# SCH_CLController.net
KiCad netlist of a schematic drawn in EasyEDA
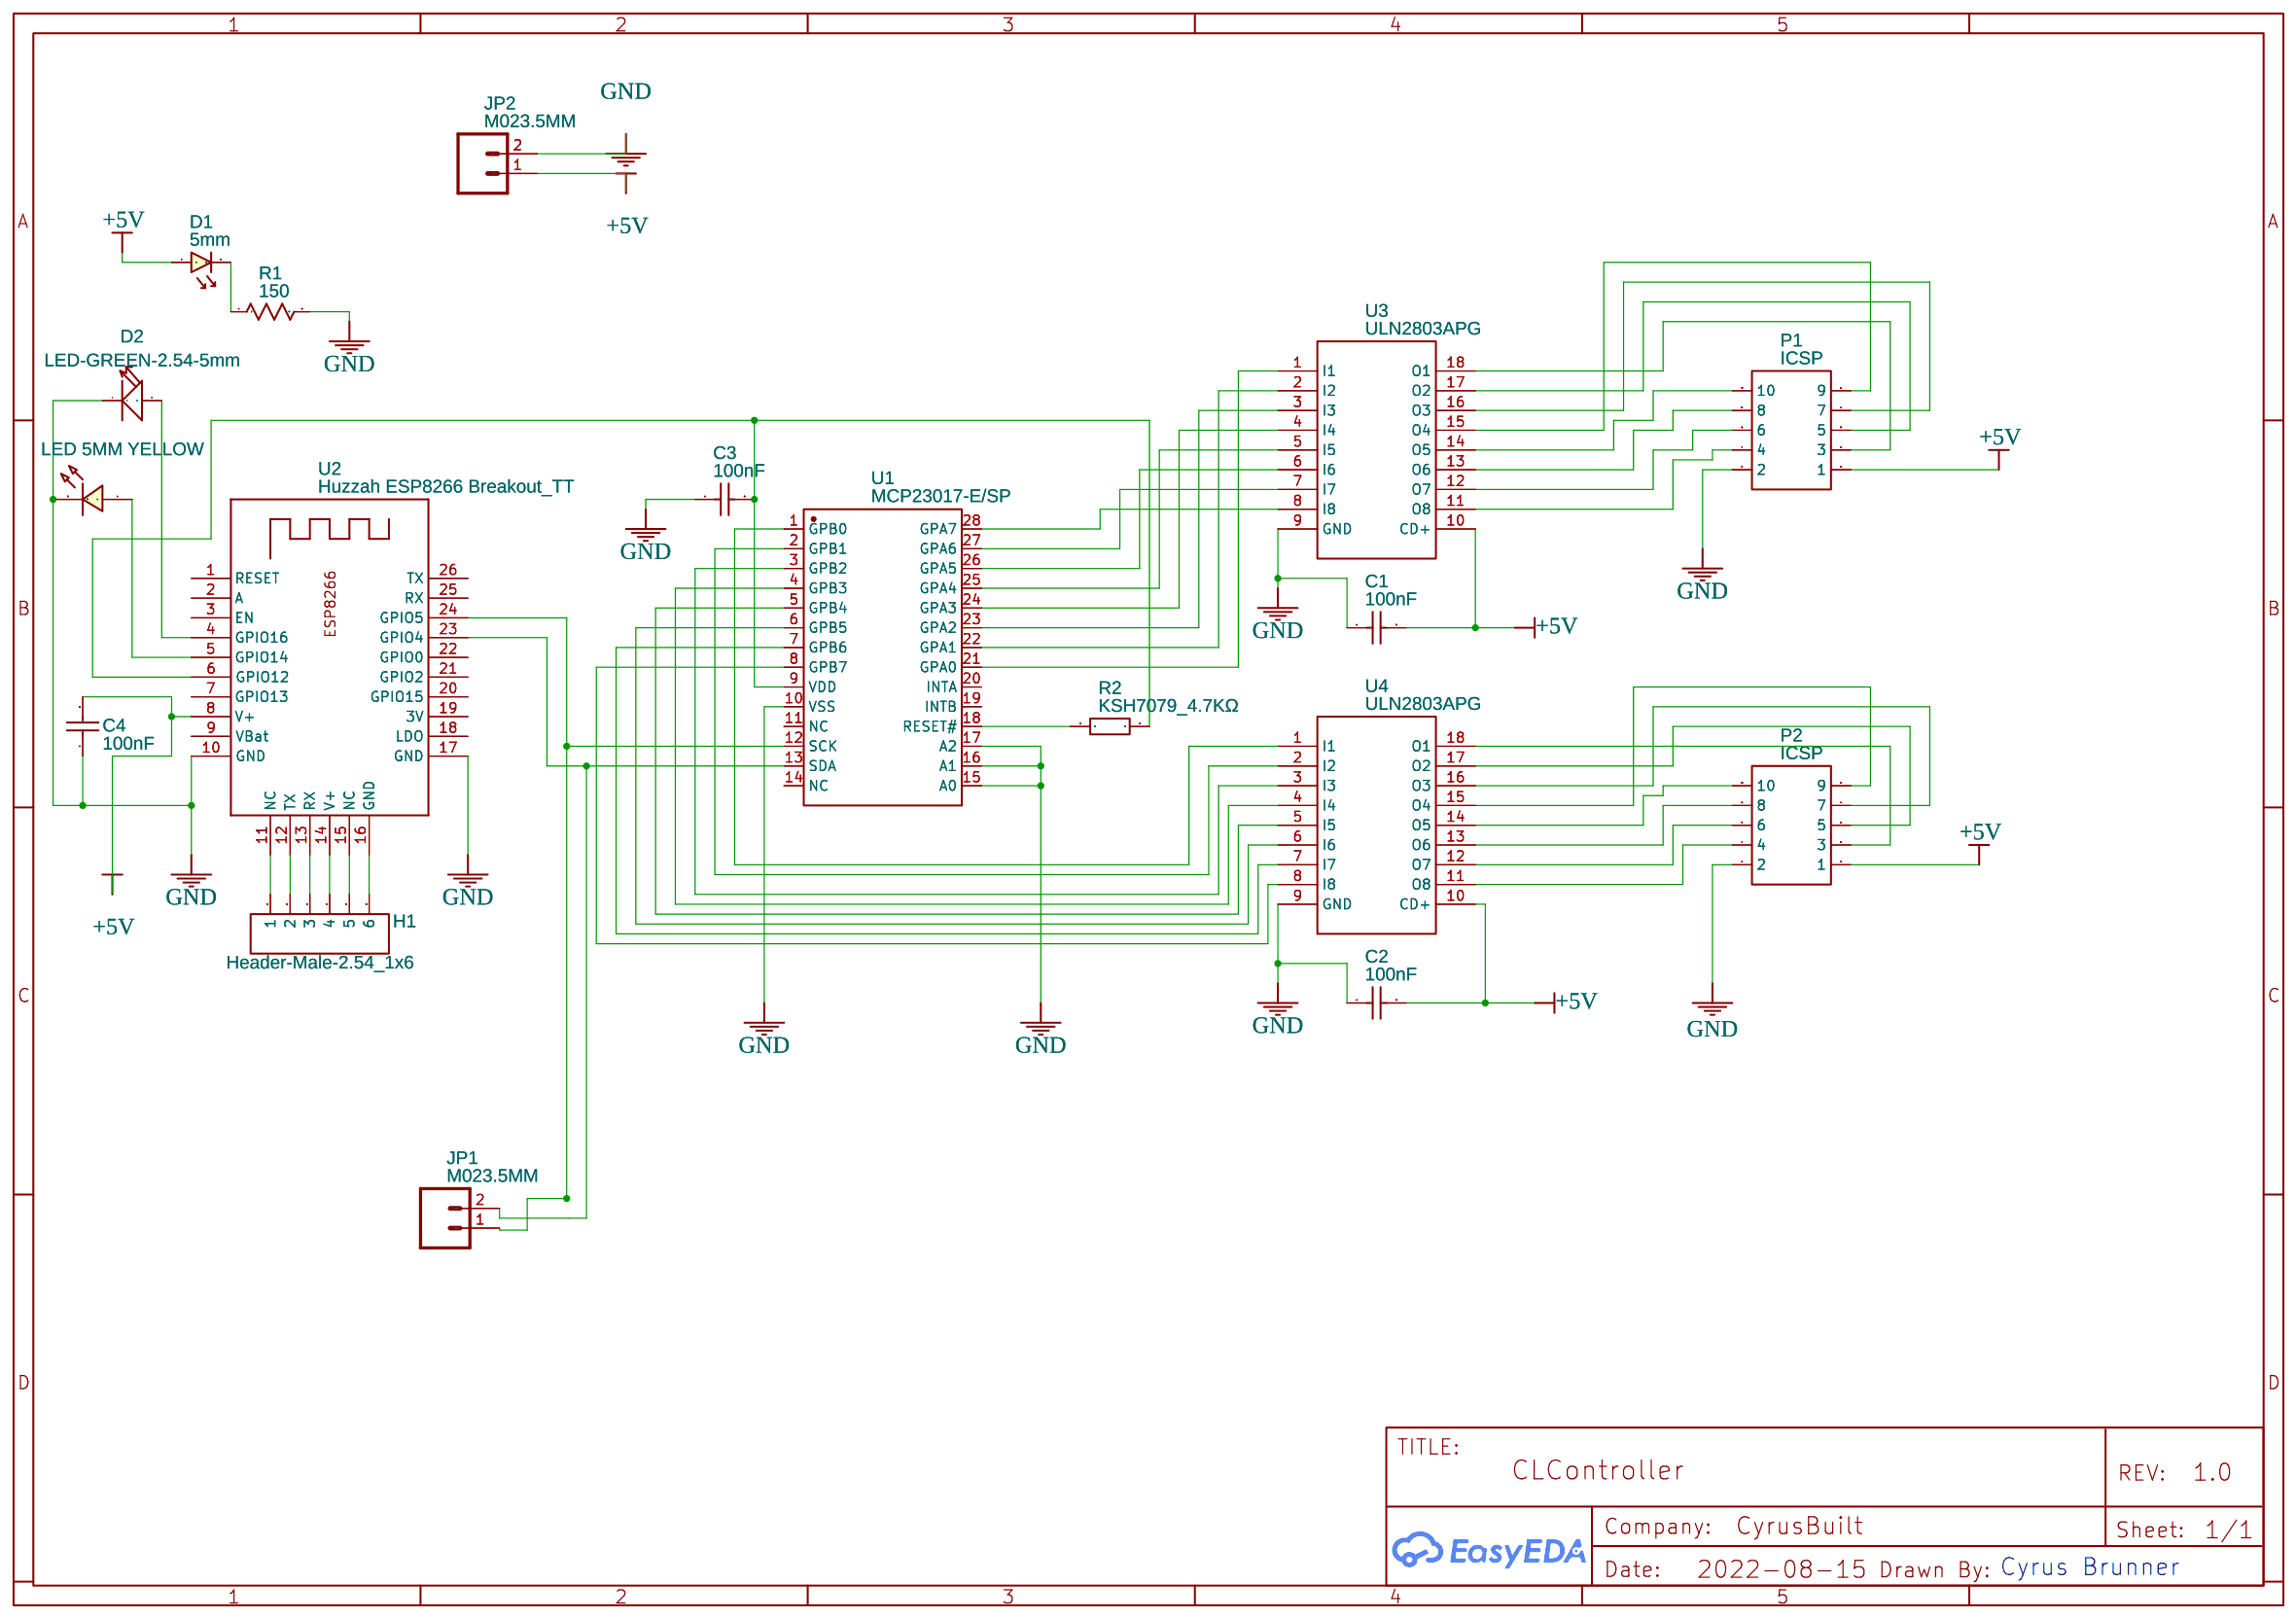
[diagram p0: schematic sheet]

(export (version "E")
  (design (tool "Eeschema 10.0.6"))
  (components
    (comp (ref "1") (value "LED 5MM YELLOW") (libsource (lib "") (part "LED 5MM YELLOW")))
    (comp (ref "C1")
      (value "100nF")
      (fields
        (field (name "BOM_Manufacturer Part") "CT4-0805Y104M500")
        (field (name "BOM_Supplier Part") "C46756")
      )
      (libsource (lib "") (part "100nF"))
    )
    (comp (ref "C2")
      (value "100nF")
      (fields
        (field (name "BOM_Manufacturer Part") "CT4-0805Y104M500")
        (field (name "BOM_Supplier Part") "C46756")
      )
      (libsource (lib "") (part "100nF"))
    )
    (comp (ref "C3")
      (value "100nF")
      (fields
        (field (name "BOM_Manufacturer Part") "CT4-0805Y104M500")
        (field (name "BOM_Supplier Part") "C46756")
      )
      (libsource (lib "") (part "100nF"))
    )
    (comp (ref "C4")
      (value "100nF")
      (fields
        (field (name "BOM_Manufacturer Part") "CT4-0805Y104M500")
        (field (name "BOM_Supplier Part") "C46756")
      )
      (libsource (lib "") (part "100nF_1"))
    )
    (comp (ref "D1")
      (value "5mm")
      (fields (field (name "BOM_Manufacturer Part") "L-1503EC") (field (name "BOM_Supplier Part") "1003201"))
      (libsource (lib "") (part "L-1503EC"))
    )
    (comp (ref "D2")
      (value "LED-GREEN-2.54-5mm")
      (fields (field (name "BOM_Manufacturer Part") "503UOC"))
      (libsource (lib "") (part "LED-GREEN-2.54-5mm"))
    )
    (comp (ref "H1")
      (value "Header-Male-2.54_1x6")
      (fields (field (name "BOM_Supplier Part") "C37208"))
      (libsource (lib "") (part "Header-Male-2.54_1x6"))
    )
    (comp (ref "JP1") (value "M023.5MM") (libsource (lib "") (part "M023.5MM")))
    (comp (ref "JP2") (value "M023.5MM") (libsource (lib "") (part "M023.5MM")))
    (comp (ref "P1")
      (value "ICSP")
      (fields
        (field (name "BOM_Manufacturer Part") "IDC Box 2.54mm 2X5P")
        (field (name "BOM_Supplier Part") "C5665")
      )
      (libsource (lib "") (part "ICSP"))
    )
    (comp (ref "P2")
      (value "ICSP")
      (fields
        (field (name "BOM_Manufacturer Part") "IDC Box 2.54mm 2X5P")
        (field (name "BOM_Supplier Part") "C5665")
      )
      (libsource (lib "") (part "ICSP"))
    )
    (comp (ref "R1")
      (value "150")
      (fields
        (field (name "BOM_Manufacturer Part") "MCF 0.25W 150R")
        (field (name "BOM_Supplier Part") "9339175")
      )
      (libsource (lib "") (part "MCF 0.25W 150R"))
    )
    (comp (ref "R2")
      (value "KSH7079_4.7KΩ")
      (fields
        (field (name "BOM_Manufacturer Part") "MFR0W4F2200A50")
        (field (name "BOM_Supplier Part") "E57439")
      )
      (libsource (lib "") (part "KSH7079_4.7KΩ"))
    )
    (comp (ref "U1")
      (value "MCP23017-E/SP")
      (fields (field (name "BOM_Supplier Part") "C647352"))
      (libsource (lib "") (part "MCP23017-E/SP"))
    )
    (comp (ref "U2")
      (value "Huzzah ESP8266 Breakout_TT")
      (libsource (lib "") (part "Huzzah ESP8266 Breakout_TT"))
    )
    (comp (ref "U3")
      (value "ULN2803APG")
      (fields (field (name "BOM_Supplier Part") "C5252"))
      (libsource (lib "") (part "ULN2803APG"))
    )
    (comp (ref "U4")
      (value "ULN2803APG")
      (fields (field (name "BOM_Supplier Part") "C5252"))
      (libsource (lib "") (part "ULN2803APG"))
    )
  )
  (nets
    (net (code "1") (name "+5V") (class "Default")
      (node (ref "C1") (pin "2") (pinfunction "2_2") (pintype "input"))
      (node (ref "C2") (pin "2") (pinfunction "2_2") (pintype "input"))
      (node (ref "C4") (pin "2") (pinfunction "2_2") (pintype "input"))
      (node (ref "D1") (pin "1") (pinfunction "1_1") (pintype "unspecified"))
      (node (ref "JP2") (pin "1") (pinfunction "1_1") (pintype "bidirectional"))
      (node (ref "P1") (pin "1") (pinfunction "1_1") (pintype "unspecified"))
      (node (ref "P2") (pin "1") (pinfunction "1_1") (pintype "unspecified"))
      (node (ref "U2") (pin "8") (pinfunction "V+_8") (pintype "bidirectional"))
      (node (ref "U3") (pin "10") (pinfunction "CD+_10") (pintype "unspecified"))
      (node (ref "U4") (pin "10") (pinfunction "CD+_10") (pintype "unspecified"))
    )
    (net (code "2") (name "GND") (class "Default")
      (node (ref "1") (pin "2") (pinfunction "2_2") (pintype "unspecified"))
      (node (ref "C1") (pin "1") (pinfunction "1_1") (pintype "input"))
      (node (ref "C2") (pin "1") (pinfunction "1_1") (pintype "input"))
      (node (ref "C3") (pin "1") (pinfunction "1_1") (pintype "input"))
      (node (ref "C4") (pin "1") (pinfunction "1_1") (pintype "input"))
      (node (ref "D2") (pin "-") (pinfunction "-_-") (pintype "unspecified"))
      (node (ref "JP2") (pin "2") (pinfunction "2_2") (pintype "bidirectional"))
      (node (ref "P1") (pin "2") (pinfunction "2_2") (pintype "unspecified"))
      (node (ref "P2") (pin "2") (pinfunction "2_2") (pintype "unspecified"))
      (node (ref "R1") (pin "2") (pinfunction "2_2") (pintype "unspecified"))
      (node (ref "U1") (pin "10") (pinfunction "VSS_10") (pintype "unspecified"))
      (node (ref "U1") (pin "15") (pinfunction "A0_15") (pintype "unspecified"))
      (node (ref "U1") (pin "16") (pinfunction "A1_16") (pintype "unspecified"))
      (node (ref "U1") (pin "17") (pinfunction "A2_17") (pintype "unspecified"))
      (node (ref "U2") (pin "10") (pinfunction "GND_10") (pintype "unspecified"))
      (node (ref "U2") (pin "17") (pinfunction "GND_17") (pintype "unspecified"))
      (node (ref "U3") (pin "9") (pinfunction "GND_9") (pintype "passive"))
      (node (ref "U4") (pin "9") (pinfunction "GND_9") (pintype "passive"))
    )
    (net (code "3") (name "Net-(D1-Pad2)") (class "Default")
      (node (ref "D1") (pin "2") (pinfunction "2_2") (pintype "unspecified"))
      (node (ref "R1") (pin "1") (pinfunction "1_1") (pintype "unspecified"))
    )
    (net (code "4") (name "Net-(H1-Pad1)") (class "Default")
      (node (ref "H1") (pin "1") (pinfunction "1_1") (pintype "input"))
      (node (ref "U2") (pin "11") (pinfunction "NC_11") (pintype "unspecified"))
    )
    (net (code "5") (name "Net-(H1-Pad2)") (class "Default")
      (node (ref "H1") (pin "2") (pinfunction "2_2") (pintype "input"))
      (node (ref "U2") (pin "12") (pinfunction "TX_12") (pintype "unspecified"))
    )
    (net (code "6") (name "Net-(H1-Pad3)") (class "Default")
      (node (ref "H1") (pin "3") (pinfunction "3_3") (pintype "input"))
      (node (ref "U2") (pin "13") (pinfunction "RX_13") (pintype "unspecified"))
    )
    (net (code "7") (name "Net-(H1-Pad4)") (class "Default")
      (node (ref "H1") (pin "4") (pinfunction "4_4") (pintype "input"))
      (node (ref "U2") (pin "14") (pinfunction "V+_14") (pintype "unspecified"))
    )
    (net (code "8") (name "Net-(H1-Pad5)") (class "Default")
      (node (ref "H1") (pin "5") (pinfunction "5_5") (pintype "input"))
      (node (ref "U2") (pin "15") (pinfunction "NC_15") (pintype "unspecified"))
    )
    (net (code "9") (name "Net-(H1-Pad6)") (class "Default")
      (node (ref "H1") (pin "6") (pinfunction "6_6") (pintype "input"))
      (node (ref "U2") (pin "16") (pinfunction "GND_16") (pintype "unspecified"))
    )
    (net (code "10") (name "Net-(U1-GPA0)") (class "Default")
      (node (ref "U1") (pin "21") (pinfunction "GPA0_21") (pintype "unspecified"))
      (node (ref "U3") (pin "1") (pinfunction "I1_1") (pintype "input"))
    )
    (net (code "11") (name "Net-(U1-GPA1)") (class "Default")
      (node (ref "U1") (pin "22") (pinfunction "GPA1_22") (pintype "unspecified"))
      (node (ref "U3") (pin "2") (pinfunction "I2_2") (pintype "input"))
    )
    (net (code "12") (name "Net-(U1-GPA2)") (class "Default")
      (node (ref "U1") (pin "23") (pinfunction "GPA2_23") (pintype "unspecified"))
      (node (ref "U3") (pin "3") (pinfunction "I3_3") (pintype "input"))
    )
    (net (code "13") (name "Net-(U1-GPA3)") (class "Default")
      (node (ref "U1") (pin "24") (pinfunction "GPA3_24") (pintype "unspecified"))
      (node (ref "U3") (pin "4") (pinfunction "I4_4") (pintype "input"))
    )
    (net (code "14") (name "Net-(U1-GPA4)") (class "Default")
      (node (ref "U1") (pin "25") (pinfunction "GPA4_25") (pintype "unspecified"))
      (node (ref "U3") (pin "5") (pinfunction "I5_5") (pintype "input"))
    )
    (net (code "15") (name "Net-(U1-GPA5)") (class "Default")
      (node (ref "U1") (pin "26") (pinfunction "GPA5_26") (pintype "unspecified"))
      (node (ref "U3") (pin "6") (pinfunction "I6_6") (pintype "input"))
    )
    (net (code "16") (name "Net-(U1-GPA6)") (class "Default")
      (node (ref "U1") (pin "27") (pinfunction "GPA6_27") (pintype "unspecified"))
      (node (ref "U3") (pin "7") (pinfunction "I7_7") (pintype "input"))
    )
    (net (code "17") (name "Net-(U1-GPA7)") (class "Default")
      (node (ref "U1") (pin "28") (pinfunction "GPA7_28") (pintype "unspecified"))
      (node (ref "U3") (pin "8") (pinfunction "I8_8") (pintype "input"))
    )
    (net (code "18") (name "Net-(U1-GPB0)") (class "Default")
      (node (ref "U1") (pin "1") (pinfunction "GPB0_1") (pintype "unspecified"))
      (node (ref "U4") (pin "1") (pinfunction "I1_1") (pintype "input"))
    )
    (net (code "19") (name "Net-(U1-GPB1)") (class "Default")
      (node (ref "U1") (pin "2") (pinfunction "GPB1_2") (pintype "unspecified"))
      (node (ref "U4") (pin "2") (pinfunction "I2_2") (pintype "input"))
    )
    (net (code "20") (name "Net-(U1-GPB2)") (class "Default")
      (node (ref "U1") (pin "3") (pinfunction "GPB2_3") (pintype "unspecified"))
      (node (ref "U4") (pin "3") (pinfunction "I3_3") (pintype "input"))
    )
    (net (code "21") (name "Net-(U1-GPB3)") (class "Default")
      (node (ref "U1") (pin "4") (pinfunction "GPB3_4") (pintype "unspecified"))
      (node (ref "U4") (pin "4") (pinfunction "I4_4") (pintype "input"))
    )
    (net (code "22") (name "Net-(U1-GPB4)") (class "Default")
      (node (ref "U1") (pin "5") (pinfunction "GPB4_5") (pintype "unspecified"))
      (node (ref "U4") (pin "5") (pinfunction "I5_5") (pintype "input"))
    )
    (net (code "23") (name "Net-(U1-GPB5)") (class "Default")
      (node (ref "U1") (pin "6") (pinfunction "GPB5_6") (pintype "unspecified"))
      (node (ref "U4") (pin "6") (pinfunction "I6_6") (pintype "input"))
    )
    (net (code "24") (name "Net-(U1-GPB6)") (class "Default")
      (node (ref "U1") (pin "7") (pinfunction "GPB6_7") (pintype "unspecified"))
      (node (ref "U4") (pin "7") (pinfunction "I7_7") (pintype "input"))
    )
    (net (code "25") (name "Net-(U1-GPB7)") (class "Default")
      (node (ref "U1") (pin "8") (pinfunction "GPB7_8") (pintype "unspecified"))
      (node (ref "U4") (pin "8") (pinfunction "I8_8") (pintype "input"))
    )
    (net (code "26") (name "Net-(U1-RESET#)") (class "Default")
      (node (ref "R2") (pin "1") (pinfunction "1_1") (pintype "input"))
      (node (ref "U1") (pin "18") (pinfunction "RESET#_18") (pintype "unspecified"))
    )
    (net (code "27") (name "Net-(U1-SCK)") (class "Default")
      (node (ref "JP1") (pin "1") (pinfunction "1_1") (pintype "bidirectional"))
      (node (ref "U1") (pin "12") (pinfunction "SCK_12") (pintype "unspecified"))
      (node (ref "U2") (pin "24") (pinfunction "GPIO5_24") (pintype "bidirectional"))
    )
    (net (code "28") (name "Net-(U1-SDA)") (class "Default")
      (node (ref "JP1") (pin "2") (pinfunction "2_2") (pintype "bidirectional"))
      (node (ref "U1") (pin "13") (pinfunction "SDA_13") (pintype "unspecified"))
      (node (ref "U2") (pin "23") (pinfunction "GPIO4_23") (pintype "bidirectional"))
    )
    (net (code "29") (name "Net-(U1-VDD)") (class "Default")
      (node (ref "C3") (pin "2") (pinfunction "2_2") (pintype "input"))
      (node (ref "R2") (pin "2") (pinfunction "2_2") (pintype "input"))
      (node (ref "U1") (pin "9") (pinfunction "VDD_9") (pintype "unspecified"))
      (node (ref "U2") (pin "6") (pinfunction "GPIO12_6") (pintype "unspecified"))
    )
    (net (code "30") (name "Net-(U2-GPIO14)") (class "Default")
      (node (ref "1") (pin "1") (pinfunction "1_1") (pintype "unspecified"))
      (node (ref "U2") (pin "5") (pinfunction "GPIO14_5") (pintype "bidirectional"))
    )
    (net (code "31") (name "Net-(U2-GPIO16)") (class "Default")
      (node (ref "D2") (pin "+") (pinfunction "+_+") (pintype "unspecified"))
      (node (ref "U2") (pin "4") (pinfunction "GPIO16_4") (pintype "bidirectional"))
    )
    (net (code "32") (name "Net-(U3-O1)") (class "Default")
      (node (ref "P1") (pin "3") (pinfunction "3_3") (pintype "unspecified"))
      (node (ref "U3") (pin "18") (pinfunction "O1_18") (pintype "unspecified"))
    )
    (net (code "33") (name "Net-(U3-O2)") (class "Default")
      (node (ref "P1") (pin "5") (pinfunction "5_5") (pintype "unspecified"))
      (node (ref "U3") (pin "17") (pinfunction "O2_17") (pintype "unspecified"))
    )
    (net (code "34") (name "Net-(U3-O3)") (class "Default")
      (node (ref "P1") (pin "7") (pinfunction "7_7") (pintype "unspecified"))
      (node (ref "U3") (pin "16") (pinfunction "O3_16") (pintype "unspecified"))
    )
    (net (code "35") (name "Net-(U3-O4)") (class "Default")
      (node (ref "P1") (pin "9") (pinfunction "9_9") (pintype "unspecified"))
      (node (ref "U3") (pin "15") (pinfunction "O4_15") (pintype "unspecified"))
    )
    (net (code "36") (name "Net-(U3-O5)") (class "Default")
      (node (ref "P1") (pin "10") (pinfunction "10_10") (pintype "unspecified"))
      (node (ref "U3") (pin "14") (pinfunction "O5_14") (pintype "unspecified"))
    )
    (net (code "37") (name "Net-(U3-O6)") (class "Default")
      (node (ref "P1") (pin "8") (pinfunction "8_8") (pintype "unspecified"))
      (node (ref "U3") (pin "13") (pinfunction "O6_13") (pintype "unspecified"))
    )
    (net (code "38") (name "Net-(U3-O7)") (class "Default")
      (node (ref "P1") (pin "6") (pinfunction "6_6") (pintype "unspecified"))
      (node (ref "U3") (pin "12") (pinfunction "O7_12") (pintype "unspecified"))
    )
    (net (code "39") (name "Net-(U3-O8)") (class "Default")
      (node (ref "P1") (pin "4") (pinfunction "4_4") (pintype "unspecified"))
      (node (ref "U3") (pin "11") (pinfunction "O8_11") (pintype "unspecified"))
    )
    (net (code "40") (name "Net-(U4-O1)") (class "Default")
      (node (ref "P2") (pin "3") (pinfunction "3_3") (pintype "unspecified"))
      (node (ref "U4") (pin "18") (pinfunction "O1_18") (pintype "unspecified"))
    )
    (net (code "41") (name "Net-(U4-O2)") (class "Default")
      (node (ref "P2") (pin "5") (pinfunction "5_5") (pintype "unspecified"))
      (node (ref "U4") (pin "17") (pinfunction "O2_17") (pintype "unspecified"))
    )
    (net (code "42") (name "Net-(U4-O3)") (class "Default")
      (node (ref "P2") (pin "7") (pinfunction "7_7") (pintype "unspecified"))
      (node (ref "U4") (pin "16") (pinfunction "O3_16") (pintype "unspecified"))
    )
    (net (code "43") (name "Net-(U4-O4)") (class "Default")
      (node (ref "P2") (pin "9") (pinfunction "9_9") (pintype "unspecified"))
      (node (ref "U4") (pin "15") (pinfunction "O4_15") (pintype "unspecified"))
    )
    (net (code "44") (name "Net-(U4-O5)") (class "Default")
      (node (ref "P2") (pin "10") (pinfunction "10_10") (pintype "unspecified"))
      (node (ref "U4") (pin "14") (pinfunction "O5_14") (pintype "unspecified"))
    )
    (net (code "45") (name "Net-(U4-O6)") (class "Default")
      (node (ref "P2") (pin "8") (pinfunction "8_8") (pintype "unspecified"))
      (node (ref "U4") (pin "13") (pinfunction "O6_13") (pintype "unspecified"))
    )
    (net (code "46") (name "Net-(U4-O7)") (class "Default")
      (node (ref "P2") (pin "6") (pinfunction "6_6") (pintype "unspecified"))
      (node (ref "U4") (pin "12") (pinfunction "O7_12") (pintype "unspecified"))
    )
    (net (code "47") (name "Net-(U4-O8)") (class "Default")
      (node (ref "P2") (pin "4") (pinfunction "4_4") (pintype "unspecified"))
      (node (ref "U4") (pin "11") (pinfunction "O8_11") (pintype "unspecified"))
    )
    (net (code "48") (name "unconnected-(U1-INTA-Pad20)") (class "Default")
      (node (ref "U1") (pin "20") (pinfunction "INTA_20") (pintype "unspecified"))
    )
    (net (code "49") (name "unconnected-(U1-INTB-Pad19)") (class "Default")
      (node (ref "U1") (pin "19") (pinfunction "INTB_19") (pintype "unspecified"))
    )
    (net (code "50") (name "unconnected-(U1-NC-Pad11)") (class "Default")
      (node (ref "U1") (pin "11") (pinfunction "NC_11") (pintype "unspecified"))
    )
    (net (code "51") (name "unconnected-(U1-NC-Pad14)") (class "Default")
      (node (ref "U1") (pin "14") (pinfunction "NC_14") (pintype "unspecified"))
    )
    (net (code "52") (name "unconnected-(U2-3V-Pad19)") (class "Default")
      (node (ref "U2") (pin "19") (pinfunction "3V_19") (pintype "unspecified"))
    )
    (net (code "53") (name "unconnected-(U2-A-Pad2)") (class "Default")
      (node (ref "U2") (pin "2") (pinfunction "A_2") (pintype "bidirectional"))
    )
    (net (code "54") (name "unconnected-(U2-EN-Pad3)") (class "Default")
      (node (ref "U2") (pin "3") (pinfunction "EN_3") (pintype "bidirectional"))
    )
    (net (code "55") (name "unconnected-(U2-GPIO0-Pad22)") (class "Default")
      (node (ref "U2") (pin "22") (pinfunction "GPIO0_22") (pintype "bidirectional"))
    )
    (net (code "56") (name "unconnected-(U2-GPIO2-Pad21)") (class "Default")
      (node (ref "U2") (pin "21") (pinfunction "GPIO2_21") (pintype "bidirectional"))
    )
    (net (code "57") (name "unconnected-(U2-GPIO13-Pad7)") (class "Default")
      (node (ref "U2") (pin "7") (pinfunction "GPIO13_7") (pintype "bidirectional"))
    )
    (net (code "58") (name "unconnected-(U2-GPIO15-Pad20)") (class "Default")
      (node (ref "U2") (pin "20") (pinfunction "GPIO15_20") (pintype "bidirectional"))
    )
    (net (code "59") (name "unconnected-(U2-LDO-Pad18)") (class "Default")
      (node (ref "U2") (pin "18") (pinfunction "LDO_18") (pintype "unspecified"))
    )
    (net (code "60") (name "unconnected-(U2-RESET-Pad1)") (class "Default")
      (node (ref "U2") (pin "1") (pinfunction "RESET_1") (pintype "bidirectional"))
    )
    (net (code "61") (name "unconnected-(U2-RX-Pad25)") (class "Default")
      (node (ref "U2") (pin "25") (pinfunction "RX_25") (pintype "bidirectional"))
    )
    (net (code "62") (name "unconnected-(U2-TX-Pad26)") (class "Default")
      (node (ref "U2") (pin "26") (pinfunction "TX_26") (pintype "bidirectional"))
    )
    (net (code "63") (name "unconnected-(U2-VBat-Pad9)") (class "Default")
      (node (ref "U2") (pin "9") (pinfunction "VBat_9") (pintype "unspecified"))
    )
  )
)
